# HDMI.net
KiCad netlist of a schematic drawn in Altium Designer
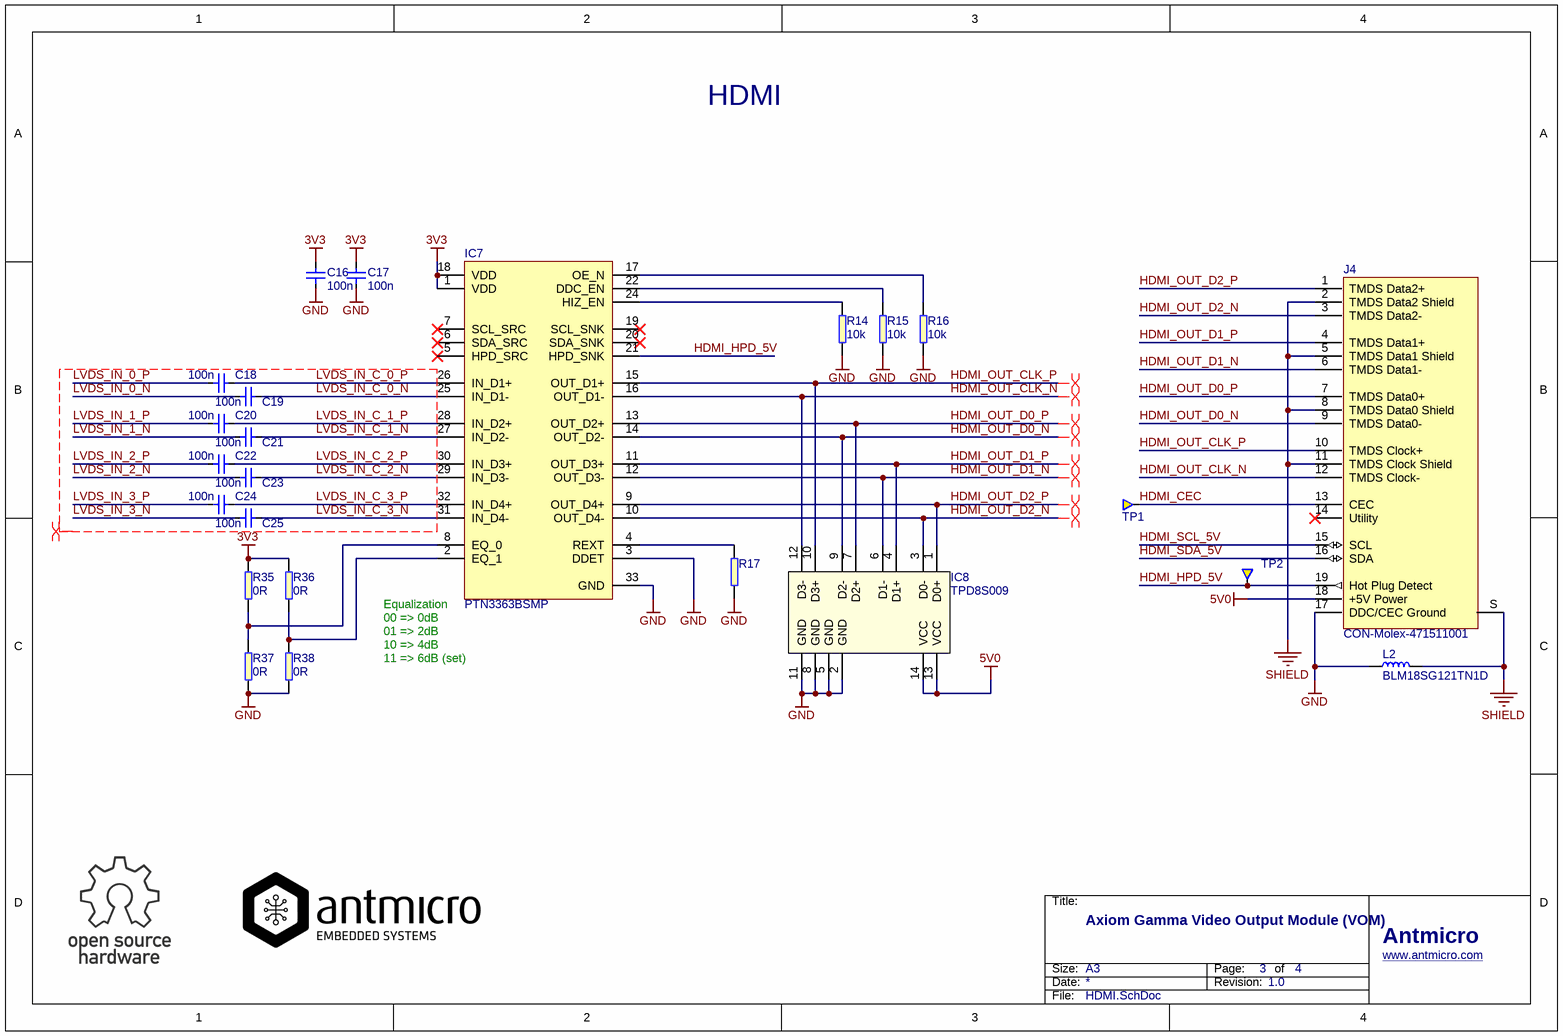
[diagram p0: HDMI.SchDoc]

(export (version "E")
  (design (tool "Eeschema 10.0.6"))
  (components
    (comp (ref "C16")
      (value "100n")
      (footprint "0402")
      (description "MLCC SMT Capacitor 0402")
      (fields (field (name "PART NUMBER") "C_100n_0402") (field (name "MANUFACTURER") "MULTICOMP"))
      (libsource (lib "VOM") (part "C_100n_0402"))
    )
    (comp (ref "C17")
      (value "100n")
      (footprint "0402")
      (description "MLCC SMT Capacitor 0402")
      (fields (field (name "PART NUMBER") "C_100n_0402") (field (name "MANUFACTURER") "MULTICOMP"))
      (libsource (lib "VOM") (part "C_100n_0402"))
    )
    (comp (ref "C18")
      (value "100n")
      (footprint "0402")
      (description "MLCC SMT Capacitor 0402")
      (fields (field (name "PART NUMBER") "C_100n_0402") (field (name "MANUFACTURER") "MULTICOMP"))
      (libsource (lib "VOM") (part "C_100n_0402"))
    )
    (comp (ref "C19")
      (value "100n")
      (footprint "0402")
      (description "MLCC SMT Capacitor 0402")
      (fields (field (name "PART NUMBER") "C_100n_0402") (field (name "MANUFACTURER") "MULTICOMP"))
      (libsource (lib "VOM") (part "C_100n_0402"))
    )
    (comp (ref "C20")
      (value "100n")
      (footprint "0402")
      (description "MLCC SMT Capacitor 0402")
      (fields (field (name "PART NUMBER") "C_100n_0402") (field (name "MANUFACTURER") "MULTICOMP"))
      (libsource (lib "VOM") (part "C_100n_0402"))
    )
    (comp (ref "C21")
      (value "100n")
      (footprint "0402")
      (description "MLCC SMT Capacitor 0402")
      (fields (field (name "PART NUMBER") "C_100n_0402") (field (name "MANUFACTURER") "MULTICOMP"))
      (libsource (lib "VOM") (part "C_100n_0402"))
    )
    (comp (ref "C22")
      (value "100n")
      (footprint "0402")
      (description "MLCC SMT Capacitor 0402")
      (fields (field (name "PART NUMBER") "C_100n_0402") (field (name "MANUFACTURER") "MULTICOMP"))
      (libsource (lib "VOM") (part "C_100n_0402"))
    )
    (comp (ref "C23")
      (value "100n")
      (footprint "0402")
      (description "MLCC SMT Capacitor 0402")
      (fields (field (name "PART NUMBER") "C_100n_0402") (field (name "MANUFACTURER") "MULTICOMP"))
      (libsource (lib "VOM") (part "C_100n_0402"))
    )
    (comp (ref "C24")
      (value "100n")
      (footprint "0402")
      (description "MLCC SMT Capacitor 0402")
      (fields (field (name "PART NUMBER") "C_100n_0402") (field (name "MANUFACTURER") "MULTICOMP"))
      (libsource (lib "VOM") (part "C_100n_0402"))
    )
    (comp (ref "C25")
      (value "100n")
      (footprint "0402")
      (description "MLCC SMT Capacitor 0402")
      (fields (field (name "PART NUMBER") "C_100n_0402") (field (name "MANUFACTURER") "MULTICOMP"))
      (libsource (lib "VOM") (part "C_100n_0402"))
    )
    (comp (ref "IC7")
      (value "PTN3363BSMP")
      (footprint "QFN-32")
      (description "HDMI level shifter")
      (fields (field (name "MANUFACTURER") "NXP"))
      (libsource (lib "VOM") (part "PTN3363"))
    )
    (comp (ref "IC8")
      (value "TPD8S009")
      (footprint "SON-15")
      (description "8-Channel ESD Protection for DisplayPort and HDMI")
      (fields (field (name "MANUFACTURER") "TEXAS INSTRUMENTS"))
      (libsource (lib "VOM") (part "TPD8S009"))
    )
    (comp (ref "J4")
      (value "CON-Molex-471511001")
      (footprint "Molex_HDMI_471511001")
      (description "Header right angle HDMI")
      (fields (field (name "MANUFACTURER") "MOLEX"))
      (libsource (lib "VOM") (part "CON-Molex-471511001"))
    )
    (comp (ref "L2")
      (value "BLM18SG121TN1D")
      (footprint "0603")
      (description "FERRITE BEAD, 0.025OHM, 3A, 0603")
      (fields (field (name "MANUFACTURER") "MURATA"))
      (libsource (lib "VOM") (part "Inductor SMT"))
    )
    (comp (ref "R14")
      (value "10k")
      (footprint "0402")
      (description "SMT Resistor 0402")
      (fields (field (name "PART NUMBER") "R_10k_0402") (field (name "MANUFACTURER") "MULTICOMP"))
      (libsource (lib "VOM") (part "R_10k_0402"))
    )
    (comp (ref "R15")
      (value "10k")
      (footprint "0402")
      (description "SMT Resistor 0402")
      (fields (field (name "PART NUMBER") "R_10k_0402") (field (name "MANUFACTURER") "MULTICOMP"))
      (libsource (lib "VOM") (part "R_10k_0402"))
    )
    (comp (ref "R16")
      (value "10k")
      (footprint "0402")
      (description "SMT Resistor 0402")
      (fields (field (name "PART NUMBER") "R_10k_0402") (field (name "MANUFACTURER") "MULTICOMP"))
      (libsource (lib "VOM") (part "R_10k_0402"))
    )
    (comp (ref "R17")
      (value "12k4")
      (footprint "0402")
      (description "SMT Resistor 12k4 0402 1%")
      (fields (field (name "PART NUMBER") "R_12k4_0402_1%") (field (name "MANUFACTURER") "MULTICOMP"))
      (libsource (lib "VOM") (part "R"))
    )
    (comp (ref "R35")
      (value "0R")
      (footprint "0603")
      (description "SMT Resistor 0R 0603")
      (fields (field (name "PART NUMBER") "R_0R_0603") (field (name "MANUFACTURER") "BOURNS"))
      (libsource (lib "VOM") (part "R_0R_0603"))
    )
    (comp (ref "R36")
      (value "0R")
      (footprint "0603")
      (description "SMT Resistor 0R 0603")
      (fields (field (name "PART NUMBER") "R_0R_0603") (field (name "MANUFACTURER") "BOURNS"))
      (libsource (lib "VOM") (part "R_0R_0603"))
    )
    (comp (ref "R37")
      (value "0R")
      (footprint "0603")
      (description "SMT Resistor 0R 0603")
      (fields (field (name "PART NUMBER") "R_0R_0603") (field (name "MANUFACTURER") "BOURNS"))
      (libsource (lib "VOM") (part "R_0R_0603"))
    )
    (comp (ref "R38")
      (value "0R")
      (footprint "0603")
      (description "SMT Resistor 0R 0603")
      (fields (field (name "PART NUMBER") "R_0R_0603") (field (name "MANUFACTURER") "BOURNS"))
      (libsource (lib "VOM") (part "R_0R_0603"))
    )
    (comp (ref "TP1")
      (value "Testpad")
      (footprint "Testpad")
      (description "Testpad 2mm diameter")
      (fields (field (name "MANUFACTURER") "PCB ONLY"))
      (libsource (lib "VOM") (part "Testpad"))
    )
    (comp (ref "TP2")
      (value "Testpad")
      (footprint "Testpad")
      (description "Testpad 2mm diameter")
      (fields (field (name "MANUFACTURER") "PCB ONLY"))
      (libsource (lib "VOM") (part "Testpad"))
    )
  )
  (nets
    (net (code "1") (name "/HDMI_CEC") (class "Default")
      (node (ref "J4") (pin "13") (pinfunction "CEC_13") (pintype "passive"))
      (node (ref "TP1") (pin "1") (pintype "passive"))
    )
    (net (code "2") (name "/HDMI_HPD_5V") (class "Default")
      (node (ref "IC7") (pin "21") (pinfunction "HPD_SNK_21") (pintype "passive"))
      (node (ref "J4") (pin "19") (pinfunction "Hot_Plug_Detect_19") (pintype "output"))
      (node (ref "TP2") (pin "1") (pintype "passive"))
    )
    (net (code "3") (name "/HDMI_OUT_CLK_N") (class "Default")
      (node (ref "IC7") (pin "16") (pinfunction "OUT_D1-_16") (pintype "passive"))
      (node (ref "IC8") (pin "12") (pinfunction "D3-_12") (pintype "passive"))
      (node (ref "J4") (pin "12") (pinfunction "TMDS_Clock-_12") (pintype "passive"))
    )
    (net (code "4") (name "/HDMI_OUT_CLK_P") (class "Default")
      (node (ref "IC7") (pin "15") (pinfunction "OUT_D1+_15") (pintype "passive"))
      (node (ref "IC8") (pin "10") (pinfunction "D3+_10") (pintype "passive"))
      (node (ref "J4") (pin "10") (pinfunction "TMDS_Clock+_10") (pintype "passive"))
    )
    (net (code "5") (name "/HDMI_OUT_D0_N") (class "Default")
      (node (ref "IC7") (pin "14") (pinfunction "OUT_D2-_14") (pintype "passive"))
      (node (ref "IC8") (pin "9") (pinfunction "D2-_9") (pintype "passive"))
      (node (ref "J4") (pin "9") (pinfunction "TMDS_Data0-_9") (pintype "passive"))
    )
    (net (code "6") (name "/HDMI_OUT_D0_P") (class "Default")
      (node (ref "IC7") (pin "13") (pinfunction "OUT_D2+_13") (pintype "passive"))
      (node (ref "IC8") (pin "7") (pinfunction "D2+_7") (pintype "passive"))
      (node (ref "J4") (pin "7") (pinfunction "TMDS_Data0+_7") (pintype "passive"))
    )
    (net (code "7") (name "/HDMI_OUT_D1_N") (class "Default")
      (node (ref "IC7") (pin "12") (pinfunction "OUT_D3-_12") (pintype "passive"))
      (node (ref "IC8") (pin "6") (pinfunction "D1-_6") (pintype "passive"))
      (node (ref "J4") (pin "6") (pinfunction "TMDS_Data1-_6") (pintype "passive"))
    )
    (net (code "8") (name "/HDMI_OUT_D1_P") (class "Default")
      (node (ref "IC7") (pin "11") (pinfunction "OUT_D3+_11") (pintype "passive"))
      (node (ref "IC8") (pin "4") (pinfunction "D1+_4") (pintype "passive"))
      (node (ref "J4") (pin "4") (pinfunction "TMDS_Data1+_4") (pintype "passive"))
    )
    (net (code "9") (name "/HDMI_OUT_D2_N") (class "Default")
      (node (ref "IC7") (pin "10") (pinfunction "OUT_D4-_10") (pintype "passive"))
      (node (ref "IC8") (pin "3") (pinfunction "D0-_3") (pintype "passive"))
      (node (ref "J4") (pin "3") (pinfunction "TMDS_Data2-_3") (pintype "passive"))
    )
    (net (code "10") (name "/HDMI_OUT_D2_P") (class "Default")
      (node (ref "IC7") (pin "9") (pinfunction "OUT_D4+_9") (pintype "passive"))
      (node (ref "IC8") (pin "1") (pinfunction "D0+_1") (pintype "passive"))
      (node (ref "J4") (pin "1") (pinfunction "TMDS_Data2+_1") (pintype "passive"))
    )
    (net (code "11") (name "/HDMI_SCL_5V") (class "Default")
      (node (ref "J4") (pin "15") (pinfunction "SCL_15") (pintype "bidirectional"))
    )
    (net (code "12") (name "/HDMI_SDA_5V") (class "Default")
      (node (ref "J4") (pin "16") (pinfunction "SDA_16") (pintype "bidirectional"))
    )
    (net (code "13") (name "/LVDS_IN_0_N") (class "Default")
      (node (ref "C19") (pin "1") (pinfunction "1_1") (pintype "passive"))
    )
    (net (code "14") (name "/LVDS_IN_0_P") (class "Default")
      (node (ref "C18") (pin "1") (pinfunction "1_1") (pintype "passive"))
    )
    (net (code "15") (name "/LVDS_IN_1_N") (class "Default")
      (node (ref "C21") (pin "1") (pinfunction "1_1") (pintype "passive"))
    )
    (net (code "16") (name "/LVDS_IN_1_P") (class "Default")
      (node (ref "C20") (pin "1") (pinfunction "1_1") (pintype "passive"))
    )
    (net (code "17") (name "/LVDS_IN_2_N") (class "Default")
      (node (ref "C23") (pin "1") (pinfunction "1_1") (pintype "passive"))
    )
    (net (code "18") (name "/LVDS_IN_2_P") (class "Default")
      (node (ref "C22") (pin "1") (pinfunction "1_1") (pintype "passive"))
    )
    (net (code "19") (name "/LVDS_IN_3_N") (class "Default")
      (node (ref "C25") (pin "1") (pinfunction "1_1") (pintype "passive"))
    )
    (net (code "20") (name "/LVDS_IN_3_P") (class "Default")
      (node (ref "C24") (pin "1") (pinfunction "1_1") (pintype "passive"))
    )
    (net (code "21") (name "/LVDS_IN_C_0_N") (class "Default")
      (node (ref "C19") (pin "2") (pinfunction "2_2") (pintype "passive"))
      (node (ref "IC7") (pin "25") (pinfunction "IN_D1-_25") (pintype "passive"))
    )
    (net (code "22") (name "/LVDS_IN_C_0_P") (class "Default")
      (node (ref "C18") (pin "2") (pinfunction "2_2") (pintype "passive"))
      (node (ref "IC7") (pin "26") (pinfunction "IN_D1+_26") (pintype "passive"))
    )
    (net (code "23") (name "/LVDS_IN_C_1_N") (class "Default")
      (node (ref "C21") (pin "2") (pinfunction "2_2") (pintype "passive"))
      (node (ref "IC7") (pin "27") (pinfunction "IN_D2-_27") (pintype "passive"))
    )
    (net (code "24") (name "/LVDS_IN_C_1_P") (class "Default")
      (node (ref "C20") (pin "2") (pinfunction "2_2") (pintype "passive"))
      (node (ref "IC7") (pin "28") (pinfunction "IN_D2+_28") (pintype "passive"))
    )
    (net (code "25") (name "/LVDS_IN_C_2_N") (class "Default")
      (node (ref "C23") (pin "2") (pinfunction "2_2") (pintype "passive"))
      (node (ref "IC7") (pin "29") (pinfunction "IN_D3-_29") (pintype "passive"))
    )
    (net (code "26") (name "/LVDS_IN_C_2_P") (class "Default")
      (node (ref "C22") (pin "2") (pinfunction "2_2") (pintype "passive"))
      (node (ref "IC7") (pin "30") (pinfunction "IN_D3+_30") (pintype "passive"))
    )
    (net (code "27") (name "/LVDS_IN_C_3_N") (class "Default")
      (node (ref "C25") (pin "2") (pinfunction "2_2") (pintype "passive"))
      (node (ref "IC7") (pin "31") (pinfunction "IN_D4-_31") (pintype "passive"))
    )
    (net (code "28") (name "/LVDS_IN_C_3_P") (class "Default")
      (node (ref "C24") (pin "2") (pinfunction "2_2") (pintype "passive"))
      (node (ref "IC7") (pin "32") (pinfunction "IN_D4+_32") (pintype "passive"))
    )
    (net (code "29") (name "3V3") (class "Default")
      (node (ref "C16") (pin "2") (pinfunction "2_2") (pintype "passive"))
      (node (ref "C17") (pin "2") (pinfunction "2_2") (pintype "passive"))
      (node (ref "IC7") (pin "1") (pinfunction "VDD_1") (pintype "passive"))
      (node (ref "IC7") (pin "18") (pinfunction "VDD_18") (pintype "passive"))
      (node (ref "R35") (pin "1") (pintype "passive"))
      (node (ref "R36") (pin "1") (pintype "passive"))
    )
    (net (code "30") (name "5V0") (class "Default")
      (node (ref "IC8") (pin "13") (pinfunction "VCC_13") (pintype "passive"))
      (node (ref "IC8") (pin "14") (pinfunction "VCC_14") (pintype "passive"))
      (node (ref "J4") (pin "18") (pinfunction "+5V_Power_18") (pintype "power_in"))
    )
    (net (code "31") (name "GND") (class "Default")
      (node (ref "C16") (pin "1") (pinfunction "1_1") (pintype "passive"))
      (node (ref "C17") (pin "1") (pinfunction "1_1") (pintype "passive"))
      (node (ref "IC7") (pin "3") (pinfunction "DDET_3") (pintype "passive"))
      (node (ref "IC7") (pin "33") (pinfunction "GND_33") (pintype "passive"))
      (node (ref "IC8") (pin "11") (pinfunction "GND_11") (pintype "passive"))
      (node (ref "IC8") (pin "2") (pinfunction "GND_2") (pintype "passive"))
      (node (ref "IC8") (pin "5") (pinfunction "GND_5") (pintype "passive"))
      (node (ref "IC8") (pin "8") (pinfunction "GND_8") (pintype "passive"))
      (node (ref "J4") (pin "17") (pinfunction "DDC/CEC_Ground_17") (pintype "power_in"))
      (node (ref "L2") (pin "1") (pintype "passive"))
      (node (ref "R14") (pin "2") (pintype "passive"))
      (node (ref "R15") (pin "2") (pintype "passive"))
      (node (ref "R16") (pin "2") (pintype "passive"))
      (node (ref "R17") (pin "1") (pintype "passive"))
      (node (ref "R37") (pin "2") (pintype "passive"))
      (node (ref "R38") (pin "2") (pintype "passive"))
    )
    (net (code "32") (name "Net-(IC7-DDC_EN)") (class "Default")
      (node (ref "IC7") (pin "22") (pinfunction "DDC_EN_22") (pintype "passive"))
      (node (ref "R15") (pin "1") (pintype "passive"))
    )
    (net (code "33") (name "Net-(IC7-EQ_0)") (class "Default")
      (node (ref "IC7") (pin "8") (pinfunction "EQ_0_8") (pintype "passive"))
      (node (ref "R35") (pin "2") (pintype "passive"))
      (node (ref "R37") (pin "1") (pintype "passive"))
    )
    (net (code "34") (name "Net-(IC7-EQ_1)") (class "Default")
      (node (ref "IC7") (pin "2") (pinfunction "EQ_1_2") (pintype "passive"))
      (node (ref "R36") (pin "2") (pintype "passive"))
      (node (ref "R38") (pin "1") (pintype "passive"))
    )
    (net (code "35") (name "Net-(IC7-HIZ_EN)") (class "Default")
      (node (ref "IC7") (pin "24") (pinfunction "HIZ_EN_24") (pintype "passive"))
      (node (ref "R14") (pin "1") (pintype "passive"))
    )
    (net (code "36") (name "Net-(IC7-OE_N)") (class "Default")
      (node (ref "IC7") (pin "17") (pinfunction "OE_N_17") (pintype "passive"))
      (node (ref "R16") (pin "1") (pintype "passive"))
    )
    (net (code "37") (name "Net-(IC7-REXT)") (class "Default")
      (node (ref "IC7") (pin "4") (pinfunction "REXT_4") (pintype "passive"))
      (node (ref "R17") (pin "2") (pintype "passive"))
    )
    (net (code "38") (name "SHIELD") (class "Default")
      (node (ref "J4") (pin "11") (pinfunction "TMDS_Clock_Shield_11") (pintype "passive"))
      (node (ref "J4") (pin "2") (pinfunction "TMDS_Data2_Shield_2") (pintype "passive"))
      (node (ref "J4") (pin "5") (pinfunction "TMDS_Data1_Shield_5") (pintype "passive"))
      (node (ref "J4") (pin "8") (pinfunction "TMDS_Data0_Shield_8") (pintype "passive"))
      (node (ref "J4") (pin "S") (pinfunction "SH_S") (pintype "passive"))
      (node (ref "L2") (pin "2") (pintype "passive"))
    )
    (net (code "39") (name "unconnected-(IC7-HPD_SRC-Pad5)") (class "Default")
      (node (ref "IC7") (pin "5") (pinfunction "HPD_SRC_5") (pintype "passive+no_connect"))
    )
    (net (code "40") (name "unconnected-(IC7-SCL_SNK-Pad19)") (class "Default")
      (node (ref "IC7") (pin "19") (pinfunction "SCL_SNK_19") (pintype "passive+no_connect"))
    )
    (net (code "41") (name "unconnected-(IC7-SCL_SRC-Pad7)") (class "Default")
      (node (ref "IC7") (pin "7") (pinfunction "SCL_SRC_7") (pintype "passive+no_connect"))
    )
    (net (code "42") (name "unconnected-(IC7-SDA_SNK-Pad20)") (class "Default")
      (node (ref "IC7") (pin "20") (pinfunction "SDA_SNK_20") (pintype "passive+no_connect"))
    )
    (net (code "43") (name "unconnected-(IC7-SDA_SRC-Pad6)") (class "Default")
      (node (ref "IC7") (pin "6") (pinfunction "SDA_SRC_6") (pintype "passive+no_connect"))
    )
    (net (code "44") (name "unconnected-(J4-Utility-Pad14)") (class "Default")
      (node (ref "J4") (pin "14") (pinfunction "Utility_14") (pintype "passive+no_connect"))
    )
  )
)
